# fameboy_button_pads.net
KiCad netlist of a schematic drawn in EAGLE
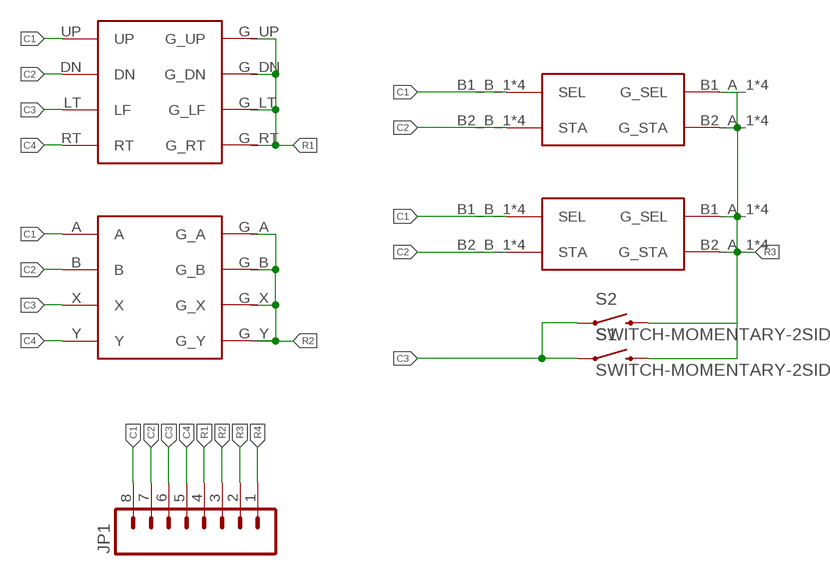
[diagram p0: schematic, sheet 1]

(export (version "E")
  (design (tool "Eeschema 10.0.6"))
  (components
    (comp (ref "JP1")
      (value "M08")
      (footprint "eagle-import:1X08_ROUND")
      (libsource (lib "eagle-import") (part "M08"))
    )
    (comp (ref "S1")
      (value "SWITCH-MOMENTARY-2SIDE")
      (footprint "eagle-import:TACTILE-PTH-SIDE")
      (libsource (lib "eagle-import") (part "SWITCH-MOMENTARY-2SIDE"))
    )
    (comp (ref "S2")
      (value "SWITCH-MOMENTARY-2SIDE")
      (footprint "eagle-import:TACTILE-PTH-SIDE")
      (libsource (lib "eagle-import") (part "SWITCH-MOMENTARY-2SIDE"))
    )
    (comp (ref "U$1")
      (value "DPADGAMEBOY_CLASSIC_DPAD")
      (footprint "eagle-import:DPAD")
      (libsource (lib "eagle-import") (part "DPADGAMEBOY_CLASSIC_DPAD"))
    )
    (comp (ref "U$2")
      (value "BAXY")
      (footprint "eagle-import:ABXY")
      (libsource (lib "eagle-import") (part "BAXY"))
    )
    (comp (ref "U$3")
      (value "SELECTSTART")
      (footprint "eagle-import:SELECTSTART")
      (libsource (lib "eagle-import") (part "SELECTSTART"))
    )
    (comp (ref "U$4")
      (value "SELECTSTART")
      (footprint "eagle-import:SELECTSTART")
      (libsource (lib "eagle-import") (part "SELECTSTART"))
    )
  )
  (nets
    (net (code "1") (name "C1") (class "Default")
      (node (ref "JP1") (pin "8") (pinfunction "8_8") (pintype "passive"))
      (node (ref "U$1") (pin "UP") (pinfunction "UP_UP") (pintype "bidirectional"))
      (node (ref "U$2") (pin "A") (pinfunction "A_A") (pintype "bidirectional"))
      (node (ref "U$3") (pin "B1_B_1") (pinfunction "SEL_B1_B_1") (pintype "bidirectional"))
      (node (ref "U$3") (pin "B1_B_2") (pinfunction "SEL_B1_B_2") (pintype "bidirectional"))
      (node (ref "U$3") (pin "B1_B_3") (pinfunction "SEL_B1_B_3") (pintype "bidirectional"))
      (node (ref "U$3") (pin "B1_B_4") (pinfunction "SEL_B1_B_4") (pintype "bidirectional"))
      (node (ref "U$4") (pin "B1_B_1") (pinfunction "SEL_B1_B_1") (pintype "bidirectional"))
      (node (ref "U$4") (pin "B1_B_2") (pinfunction "SEL_B1_B_2") (pintype "bidirectional"))
      (node (ref "U$4") (pin "B1_B_3") (pinfunction "SEL_B1_B_3") (pintype "bidirectional"))
      (node (ref "U$4") (pin "B1_B_4") (pinfunction "SEL_B1_B_4") (pintype "bidirectional"))
    )
    (net (code "2") (name "C2") (class "Default")
      (node (ref "JP1") (pin "7") (pinfunction "7_7") (pintype "passive"))
      (node (ref "U$1") (pin "DN") (pinfunction "DN_DN") (pintype "bidirectional"))
      (node (ref "U$2") (pin "B") (pinfunction "B_B") (pintype "bidirectional"))
      (node (ref "U$3") (pin "B2_B_1") (pinfunction "STA_B2_B_1") (pintype "bidirectional"))
      (node (ref "U$3") (pin "B2_B_2") (pinfunction "STA_B2_B_2") (pintype "bidirectional"))
      (node (ref "U$3") (pin "B2_B_3") (pinfunction "STA_B2_B_3") (pintype "bidirectional"))
      (node (ref "U$3") (pin "B2_B_4") (pinfunction "STA_B2_B_4") (pintype "bidirectional"))
      (node (ref "U$4") (pin "B2_B_1") (pinfunction "STA_B2_B_1") (pintype "bidirectional"))
      (node (ref "U$4") (pin "B2_B_2") (pinfunction "STA_B2_B_2") (pintype "bidirectional"))
      (node (ref "U$4") (pin "B2_B_3") (pinfunction "STA_B2_B_3") (pintype "bidirectional"))
      (node (ref "U$4") (pin "B2_B_4") (pinfunction "STA_B2_B_4") (pintype "bidirectional"))
    )
    (net (code "3") (name "C3") (class "Default")
      (node (ref "JP1") (pin "6") (pinfunction "6_6") (pintype "passive"))
      (node (ref "S1") (pin "1") (pinfunction "1_1") (pintype "passive"))
      (node (ref "S2") (pin "1") (pinfunction "1_1") (pintype "passive"))
      (node (ref "U$1") (pin "LT") (pinfunction "LF_LT") (pintype "bidirectional"))
      (node (ref "U$2") (pin "X") (pinfunction "X_X") (pintype "bidirectional"))
    )
    (net (code "4") (name "C4") (class "Default")
      (node (ref "JP1") (pin "5") (pinfunction "5_5") (pintype "passive"))
      (node (ref "U$1") (pin "RT") (pinfunction "RT_RT") (pintype "bidirectional"))
      (node (ref "U$2") (pin "Y") (pinfunction "Y_Y") (pintype "bidirectional"))
    )
    (net (code "5") (name "R1") (class "Default")
      (node (ref "JP1") (pin "4") (pinfunction "4_4") (pintype "passive"))
      (node (ref "U$1") (pin "G_DN") (pinfunction "G_DN_G_DN") (pintype "bidirectional"))
      (node (ref "U$1") (pin "G_LT") (pinfunction "G_LF_G_LT") (pintype "bidirectional"))
      (node (ref "U$1") (pin "G_RT") (pinfunction "G_RT_G_RT") (pintype "bidirectional"))
      (node (ref "U$1") (pin "G_UP") (pinfunction "G_UP_G_UP") (pintype "bidirectional"))
    )
    (net (code "6") (name "R2") (class "Default")
      (node (ref "JP1") (pin "3") (pinfunction "3_3") (pintype "passive"))
      (node (ref "U$2") (pin "G_A") (pinfunction "G_A_G_A") (pintype "bidirectional"))
      (node (ref "U$2") (pin "G_B") (pinfunction "G_B_G_B") (pintype "bidirectional"))
      (node (ref "U$2") (pin "G_X") (pinfunction "G_X_G_X") (pintype "bidirectional"))
      (node (ref "U$2") (pin "G_Y") (pinfunction "G_Y_G_Y") (pintype "bidirectional"))
    )
    (net (code "7") (name "R3") (class "Default")
      (node (ref "JP1") (pin "2") (pinfunction "2_2") (pintype "passive"))
      (node (ref "S1") (pin "2") (pinfunction "2_2") (pintype "passive"))
      (node (ref "S2") (pin "2") (pinfunction "2_2") (pintype "passive"))
      (node (ref "U$3") (pin "B1_A_1") (pinfunction "G_SEL_B1_A_1") (pintype "bidirectional"))
      (node (ref "U$3") (pin "B1_A_2") (pinfunction "G_SEL_B1_A_2") (pintype "bidirectional"))
      (node (ref "U$3") (pin "B1_A_3") (pinfunction "G_SEL_B1_A_3") (pintype "bidirectional"))
      (node (ref "U$3") (pin "B1_A_4") (pinfunction "G_SEL_B1_A_4") (pintype "bidirectional"))
      (node (ref "U$3") (pin "B2_A_1") (pinfunction "G_STA_B2_A_1") (pintype "bidirectional"))
      (node (ref "U$3") (pin "B2_A_2") (pinfunction "G_STA_B2_A_2") (pintype "bidirectional"))
      (node (ref "U$3") (pin "B2_A_3") (pinfunction "G_STA_B2_A_3") (pintype "bidirectional"))
      (node (ref "U$3") (pin "B2_A_4") (pinfunction "G_STA_B2_A_4") (pintype "bidirectional"))
      (node (ref "U$4") (pin "B1_A_1") (pinfunction "G_SEL_B1_A_1") (pintype "bidirectional"))
      (node (ref "U$4") (pin "B1_A_2") (pinfunction "G_SEL_B1_A_2") (pintype "bidirectional"))
      (node (ref "U$4") (pin "B1_A_3") (pinfunction "G_SEL_B1_A_3") (pintype "bidirectional"))
      (node (ref "U$4") (pin "B1_A_4") (pinfunction "G_SEL_B1_A_4") (pintype "bidirectional"))
      (node (ref "U$4") (pin "B2_A_1") (pinfunction "G_STA_B2_A_1") (pintype "bidirectional"))
      (node (ref "U$4") (pin "B2_A_2") (pinfunction "G_STA_B2_A_2") (pintype "bidirectional"))
      (node (ref "U$4") (pin "B2_A_3") (pinfunction "G_STA_B2_A_3") (pintype "bidirectional"))
      (node (ref "U$4") (pin "B2_A_4") (pinfunction "G_STA_B2_A_4") (pintype "bidirectional"))
    )
    (net (code "8") (name "R4") (class "Default")
      (node (ref "JP1") (pin "1") (pinfunction "1_1") (pintype "passive"))
    )
  )
)
